# Schematic1.net
KiCad netlist of a schematic drawn in EAGLE
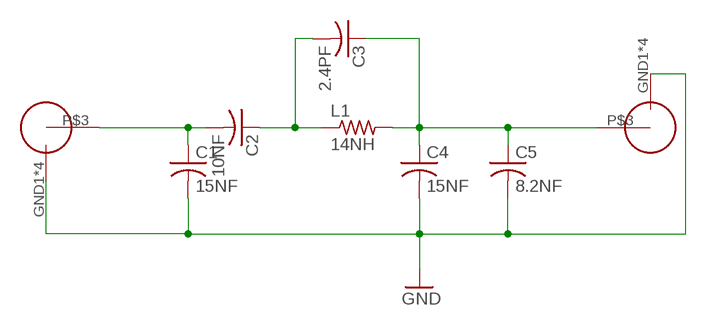
[diagram p0: schematic, sheet 1]

(export (version "E")
  (design (tool "Eeschema 10.0.6"))
  (components
    (comp (ref "C1")
      (value "15NF")
      (footprint "eagle-import:C0603")
      (libsource (lib "eagle-import") (part "C-USC0603"))
    )
    (comp (ref "C2")
      (value "10NF")
      (footprint "eagle-import:C0603")
      (libsource (lib "eagle-import") (part "C-USC0603"))
    )
    (comp (ref "C3")
      (value "2.4PF")
      (footprint "eagle-import:C0603")
      (libsource (lib "eagle-import") (part "C-USC0603"))
    )
    (comp (ref "C4")
      (value "15NF")
      (footprint "eagle-import:C0603")
      (libsource (lib "eagle-import") (part "C-USC0603"))
    )
    (comp (ref "C5")
      (value "8.2NF")
      (footprint "eagle-import:C0603")
      (libsource (lib "eagle-import") (part "C-USC0603"))
    )
    (comp (ref "GND")
      (value "SMAJ716-ND")
      (footprint "eagle-import:SMAJ716-ND")
      (libsource (lib "eagle-import") (part "SMAJ716-ND"))
    )
    (comp (ref "L1")
      (value "14NH")
      (footprint "eagle-import:R0603")
      (libsource (lib "eagle-import") (part "R-US_R0603"))
    )
    (comp (ref "U$2")
      (value "SMAJ716-ND")
      (footprint "eagle-import:SMAJ716-ND")
      (libsource (lib "eagle-import") (part "SMAJ716-ND"))
    )
  )
  (nets
    (net (code "1") (name "GND") (class "Default")
      (node (ref "C1") (pin "2") (pinfunction "2_2") (pintype "passive"))
      (node (ref "C4") (pin "2") (pinfunction "2_2") (pintype "passive"))
      (node (ref "C5") (pin "2") (pinfunction "2_2") (pintype "passive"))
      (node (ref "GND") (pin "GND1") (pinfunction "OUTERCONDUCTOR_GND1") (pintype "bidirectional"))
      (node (ref "GND") (pin "GND2") (pinfunction "OUTERCONDUCTOR_GND2") (pintype "bidirectional"))
      (node (ref "GND") (pin "GND3") (pinfunction "OUTERCONDUCTOR_GND3") (pintype "bidirectional"))
      (node (ref "GND") (pin "GND4") (pinfunction "OUTERCONDUCTOR_GND4") (pintype "bidirectional"))
      (node (ref "U$2") (pin "GND1") (pinfunction "OUTERCONDUCTOR_GND1") (pintype "bidirectional"))
      (node (ref "U$2") (pin "GND2") (pinfunction "OUTERCONDUCTOR_GND2") (pintype "bidirectional"))
      (node (ref "U$2") (pin "GND3") (pinfunction "OUTERCONDUCTOR_GND3") (pintype "bidirectional"))
      (node (ref "U$2") (pin "GND4") (pinfunction "OUTERCONDUCTOR_GND4") (pintype "bidirectional"))
    )
    (net (code "2") (name "Net-(C2-Pad1)") (class "Default")
      (node (ref "C2") (pin "1") (pinfunction "1_1") (pintype "passive"))
      (node (ref "C3") (pin "2") (pinfunction "2_2") (pintype "passive"))
      (node (ref "L1") (pin "1") (pinfunction "1_1") (pintype "passive"))
    )
    (net (code "3") (name "Net-(GND-CENTERCONDUCTOR)") (class "Default")
      (node (ref "C1") (pin "1") (pinfunction "1_1") (pintype "passive"))
      (node (ref "C2") (pin "2") (pinfunction "2_2") (pintype "passive"))
      (node (ref "GND") (pin "P$3") (pinfunction "CENTERCONDUCTOR_P$3") (pintype "bidirectional"))
    )
    (net (code "4") (name "Net-(U$2-CENTERCONDUCTOR)") (class "Default")
      (node (ref "C3") (pin "1") (pinfunction "1_1") (pintype "passive"))
      (node (ref "C4") (pin "1") (pinfunction "1_1") (pintype "passive"))
      (node (ref "C5") (pin "1") (pinfunction "1_1") (pintype "passive"))
      (node (ref "L1") (pin "2") (pinfunction "2_2") (pintype "passive"))
      (node (ref "U$2") (pin "P$3") (pinfunction "CENTERCONDUCTOR_P$3") (pintype "bidirectional"))
    )
  )
)
